# SCH_BusinessCard_2024-06-30_1.net
KiCad netlist of a schematic drawn in EasyEDA
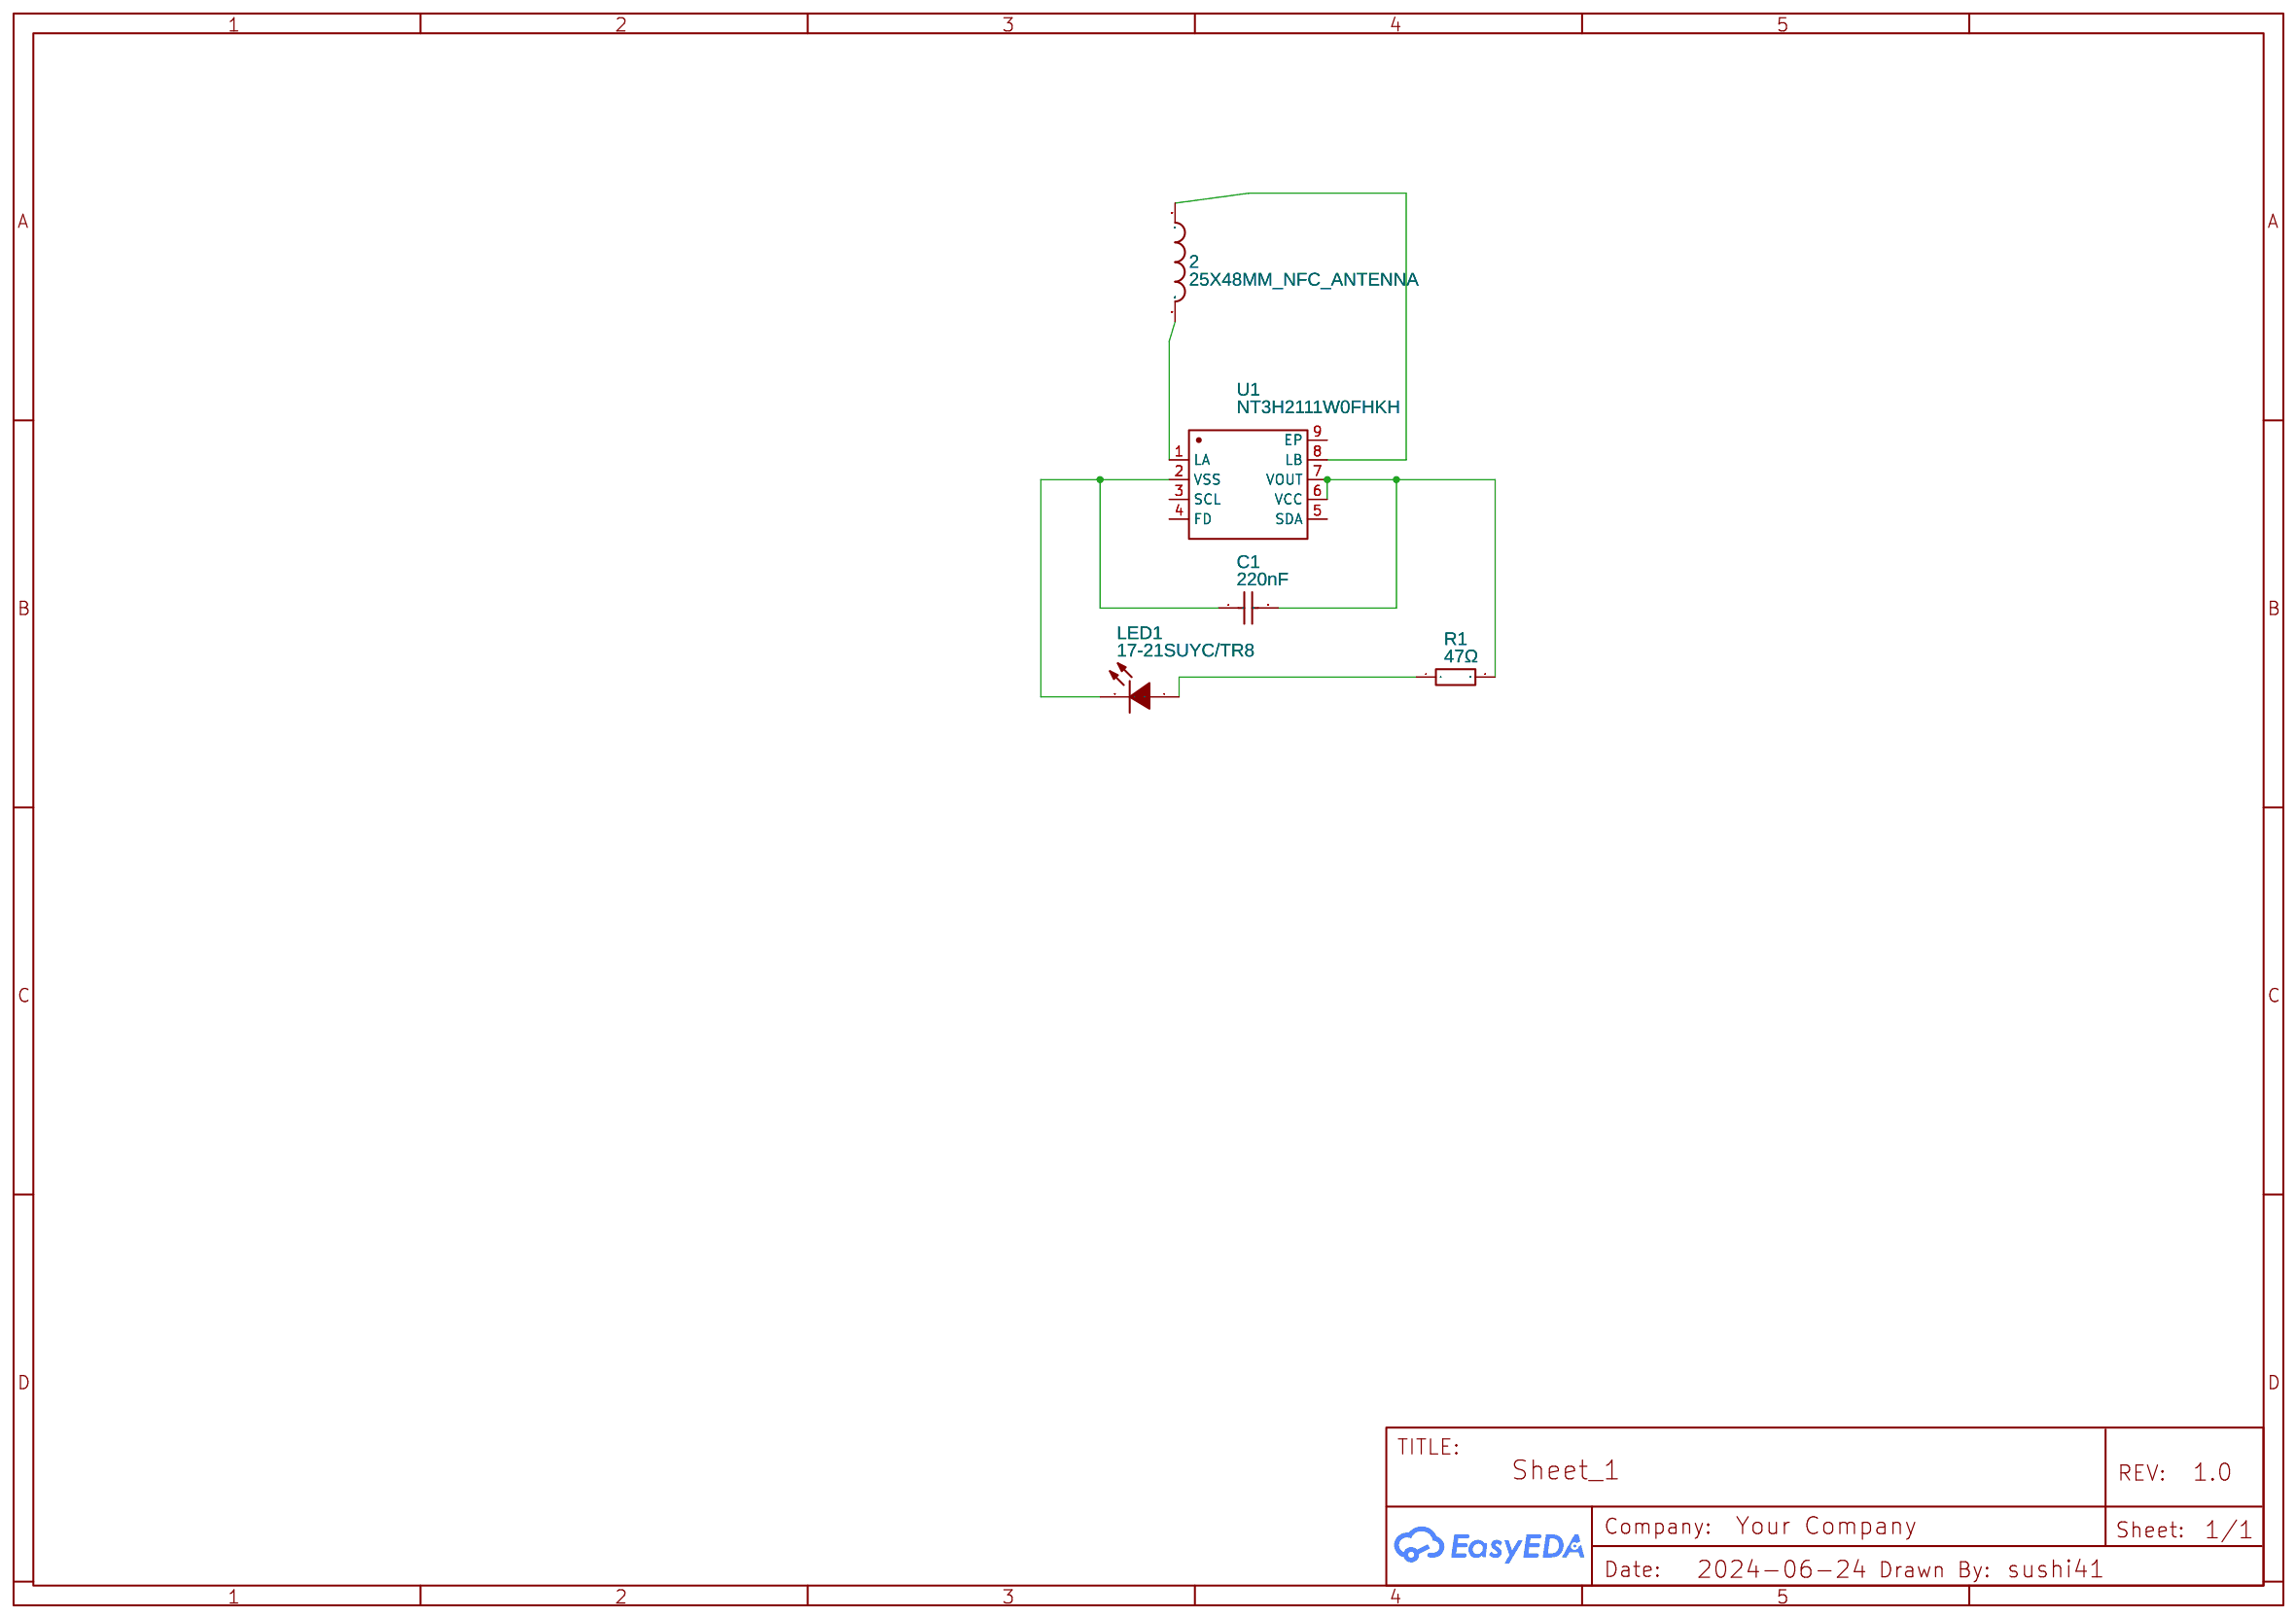
[diagram p0: schematic sheet]

(export (version "E")
  (design (tool "Eeschema 10.0.6"))
  (components
    (comp (ref "2") (value "25X48MM_NFC_ANTENNA") (libsource (lib "") (part "25X48MM_NFC_ANTENNA")))
    (comp (ref "C1")
      (value "220nF")
      (fields
        (field (name "Manufacturer Part") "CL10B224KA8NNNC")
        (field (name "Manufacturer") "SAMSUNG(三星)")
      )
      (libsource (lib "") (part "CL10B224KA8NNNC"))
    )
    (comp (ref "LED1")
      (value "17-21SUYC/TR8")
      (fields (field (name "Manufacturer Part") "KT-0805黄灯") (field (name "Manufacturer") "KENTO"))
      (libsource (lib "") (part "17-21SUYC/TR8"))
    )
    (comp (ref "R1")
      (value "47Ω")
      (fields
        (field (name "Manufacturer Part") "0603WAF470JT5E")
        (field (name "Manufacturer") "UNI-ROYAL(厚声)")
      )
      (libsource (lib "") (part "0603WAF470JT5E"))
    )
    (comp (ref "U1")
      (value "NT3H2111W0FHKH")
      (fields (field (name "Manufacturer") "NXP(恩智浦)"))
      (libsource (lib "") (part "NT3H2111W0FHKH"))
    )
  )
  (nets
    (net (code "1") (name "Net-(LED1-+)") (class "Default")
      (node (ref "LED1") (pin "1") (pinfunction "+_1") (pintype "unspecified"))
      (node (ref "R1") (pin "1") (pinfunction "1_1") (pintype "input"))
    )
    (net (code "2") (name "Net-(LED1--)") (class "Default")
      (node (ref "C1") (pin "1") (pinfunction "1_1") (pintype "input"))
      (node (ref "LED1") (pin "2") (pinfunction "-_2") (pintype "unspecified"))
      (node (ref "U1") (pin "2") (pinfunction "VSS_2") (pintype "unspecified"))
    )
    (net (code "3") (name "Net-(U1-LA)") (class "Default")
      (node (ref "2") (pin "P$2") (pinfunction "P$2_P$2") (pintype "bidirectional"))
      (node (ref "U1") (pin "1") (pinfunction "LA_1") (pintype "unspecified"))
    )
    (net (code "4") (name "Net-(U1-LB)") (class "Default")
      (node (ref "2") (pin "P$1") (pinfunction "P$1_P$1") (pintype "bidirectional"))
      (node (ref "U1") (pin "8") (pinfunction "LB_8") (pintype "unspecified"))
    )
    (net (code "5") (name "Net-(U1-VCC)") (class "Default")
      (node (ref "C1") (pin "2") (pinfunction "2_2") (pintype "input"))
      (node (ref "R1") (pin "2") (pinfunction "2_2") (pintype "input"))
      (node (ref "U1") (pin "6") (pinfunction "VCC_6") (pintype "unspecified"))
      (node (ref "U1") (pin "7") (pinfunction "VOUT_7") (pintype "unspecified"))
    )
    (net (code "6") (name "unconnected-(U1-EP-Pad9)") (class "Default")
      (node (ref "U1") (pin "9") (pinfunction "EP_9") (pintype "unspecified"))
    )
    (net (code "7") (name "unconnected-(U1-FD-Pad4)") (class "Default")
      (node (ref "U1") (pin "4") (pinfunction "FD_4") (pintype "unspecified"))
    )
    (net (code "8") (name "unconnected-(U1-SCL-Pad3)") (class "Default")
      (node (ref "U1") (pin "3") (pinfunction "SCL_3") (pintype "unspecified"))
    )
    (net (code "9") (name "unconnected-(U1-SDA-Pad5)") (class "Default")
      (node (ref "U1") (pin "5") (pinfunction "SDA_5") (pintype "unspecified"))
    )
  )
)
